# Sheet2.net
KiCad netlist of a schematic drawn in Altium Designer
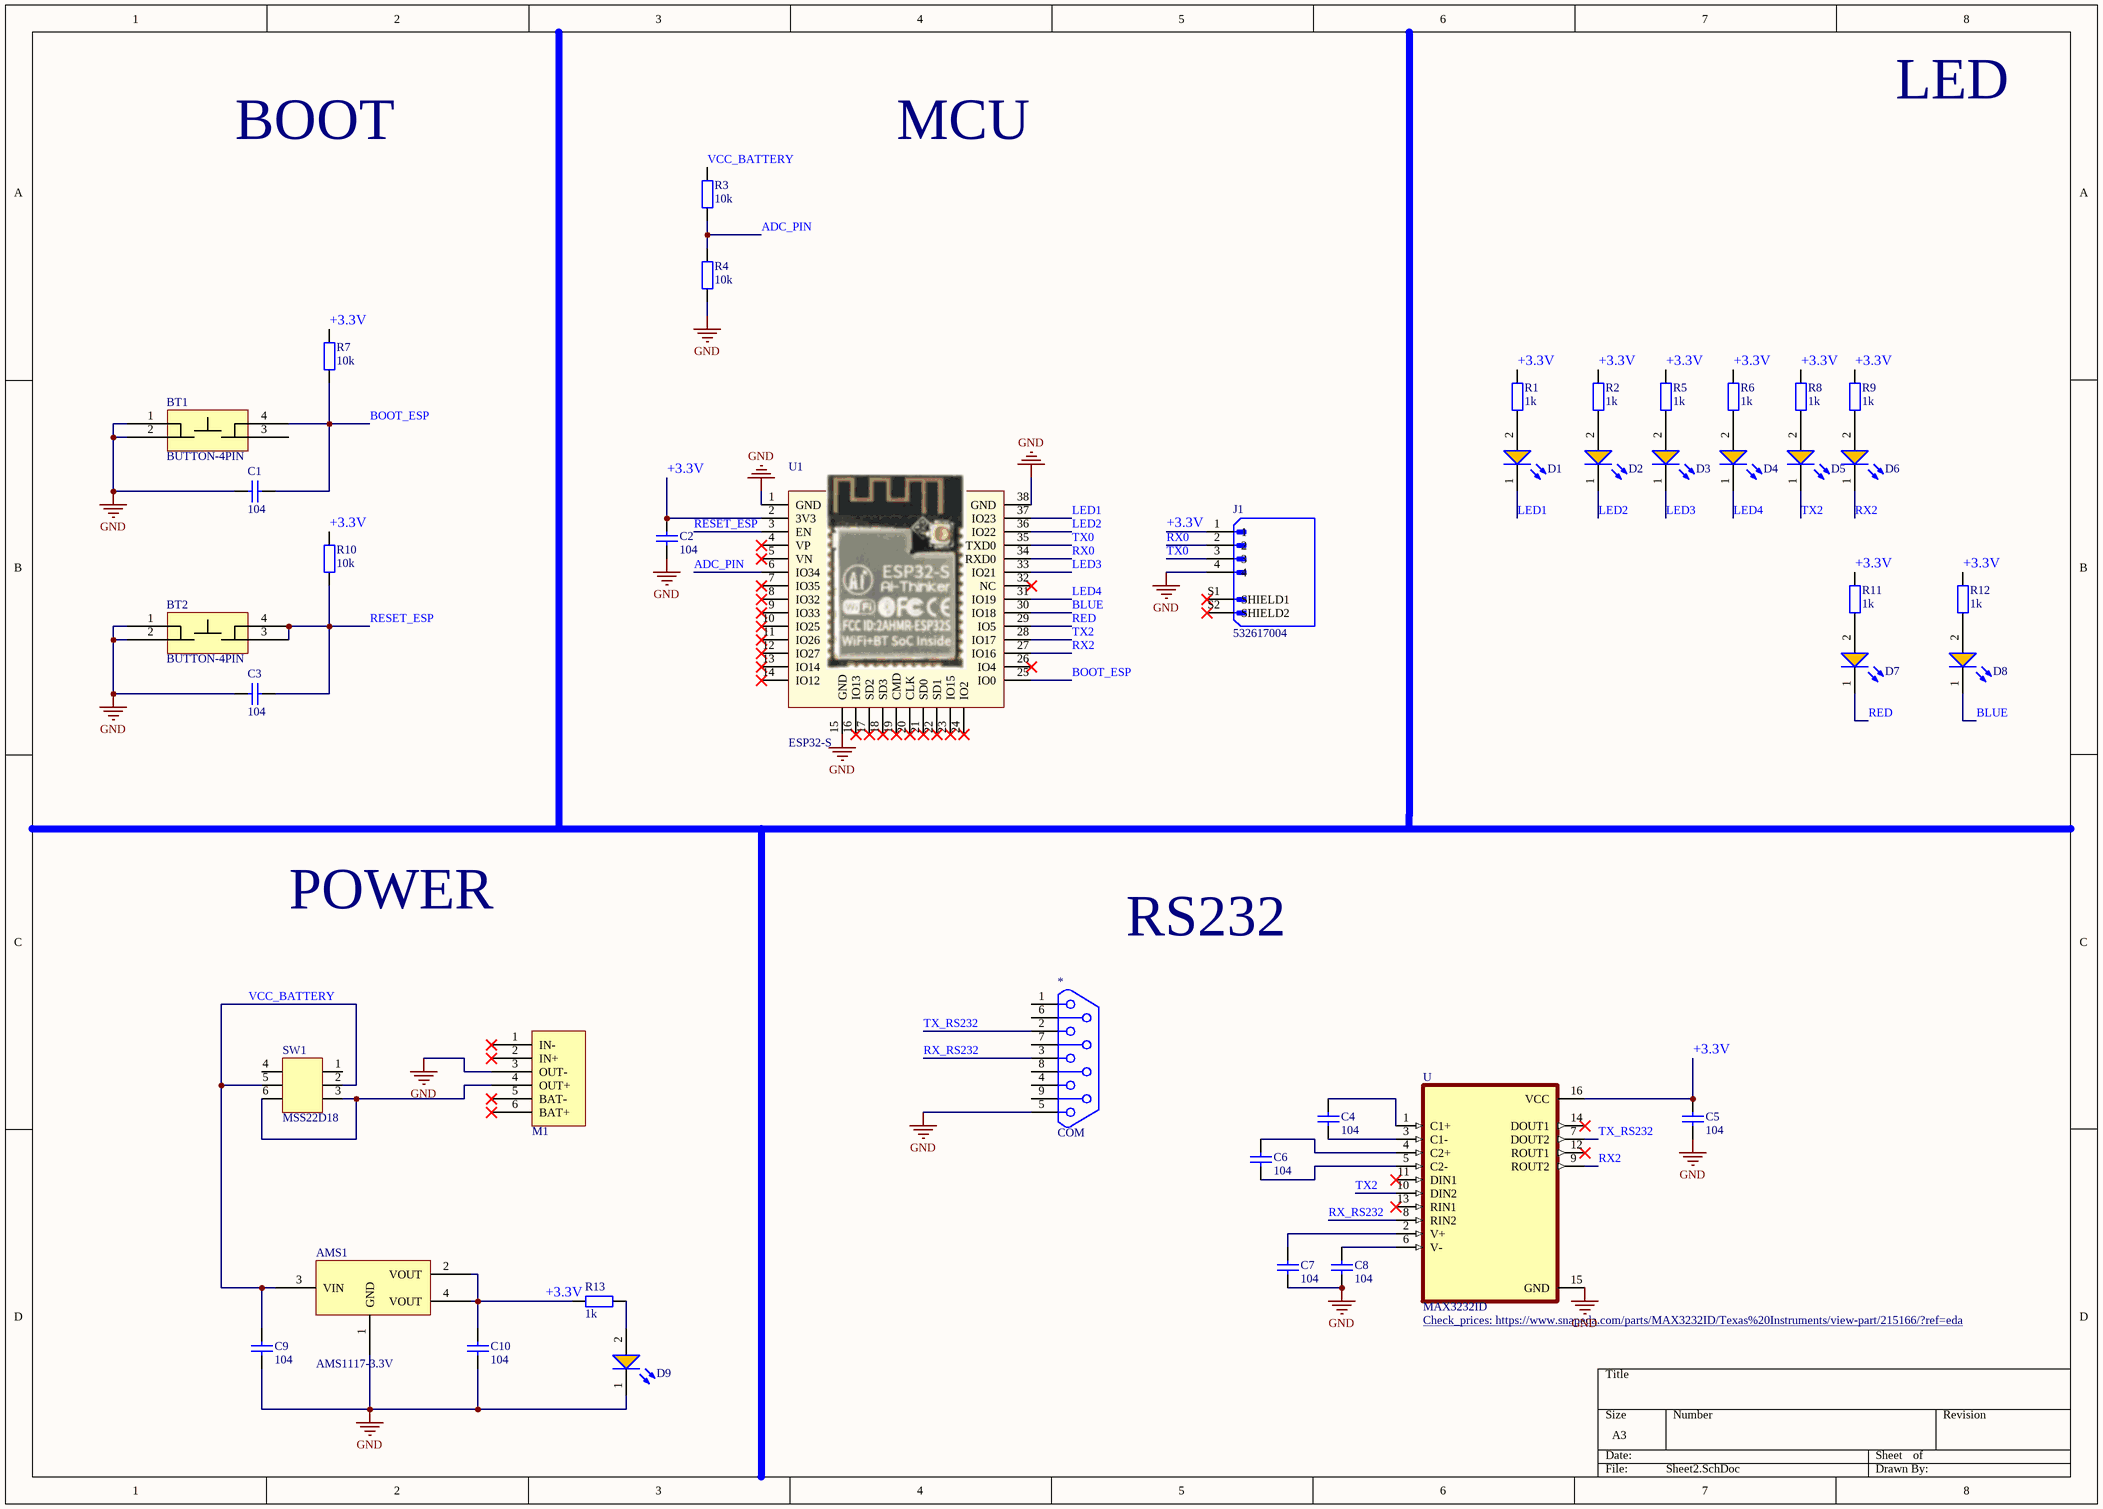
[diagram p0: Sheet2.SchDoc]

(export (version "E")
  (design (tool "Eeschema 10.0.6"))
  (components
    (comp (ref "*") (value "COM") (footprint "DSB 9-M") (libsource (lib "syhaunguyen") (part "COM")))
    (comp (ref "AMS1")
      (value "AMS1117-3.3V")
      (footprint "SOT223")
      (description "Dán")
      (libsource (lib "Altium_Lib_by_KhueNguyenCreator") (part "AMS1117 SMD"))
    )
    (comp (ref "BT1")
      (value "BUTTON-4PIN")
      (footprint "BUTTON-3X3X1.5-4PIN")
      (libsource (lib "THU_VIEN_1") (part "BUTTON-4PIN"))
    )
    (comp (ref "BT2")
      (value "BUTTON-4PIN")
      (footprint "BUTTON-3X3X1.5-4PIN")
      (libsource (lib "THU_VIEN_1") (part "BUTTON-4PIN"))
    )
    (comp (ref "C1")
      (value "104")
      (footprint "tu 0603")
      (description "Dán")
      (libsource (lib "Altium_Lib_by_KhueNguyenCreator") (part "Tu 0603 104 50V 10%"))
    )
    (comp (ref "C2")
      (value "104")
      (footprint "tu 0603")
      (description "Dán")
      (libsource (lib "Altium_Lib_by_KhueNguyenCreator") (part "Tu 0603 104 50V 10%"))
    )
    (comp (ref "C3")
      (value "104")
      (footprint "tu 0603")
      (description "Dán")
      (libsource (lib "Altium_Lib_by_KhueNguyenCreator") (part "Tu 0603 104 50V 10%"))
    )
    (comp (ref "C4")
      (value "104")
      (footprint "tu 0603")
      (description "Dán")
      (libsource (lib "Altium_Lib_by_KhueNguyenCreator") (part "Tu 0603 104 50V 10%"))
    )
    (comp (ref "C5")
      (value "104")
      (footprint "tu 0603")
      (description "Dán")
      (libsource (lib "Altium_Lib_by_KhueNguyenCreator") (part "Tu 0603 104 50V 10%"))
    )
    (comp (ref "C6")
      (value "104")
      (footprint "tu 0603")
      (description "Dán")
      (libsource (lib "Altium_Lib_by_KhueNguyenCreator") (part "Tu 0603 104 50V 10%"))
    )
    (comp (ref "C7")
      (value "104")
      (footprint "tu 0603")
      (description "Dán")
      (libsource (lib "Altium_Lib_by_KhueNguyenCreator") (part "Tu 0603 104 50V 10%"))
    )
    (comp (ref "C8")
      (value "104")
      (footprint "tu 0603")
      (description "Dán")
      (libsource (lib "Altium_Lib_by_KhueNguyenCreator") (part "Tu 0603 104 50V 10%"))
    )
    (comp (ref "C9")
      (value "104")
      (footprint "tu 0603")
      (description "Dán")
      (libsource (lib "Altium_Lib_by_KhueNguyenCreator") (part "Tu 0603 104 50V 10%"))
    )
    (comp (ref "C10")
      (value "104")
      (footprint "tu 0603")
      (description "Dán")
      (libsource (lib "Altium_Lib_by_KhueNguyenCreator") (part "Tu 0603 104 50V 10%"))
    )
    (comp (ref "D1")
      (value "Amber, 2V, 120°")
      (footprint "WL-SMSW_0603_L1.6W1H0.6")
      (description "WL-SMSW Mono-color Side View Waterclear, size 0603, Amber, 2V, 120°")
      (fields
        (field (name "MANUFACTURER PART NUMBER") "155060AS73200")
        (field (name "MANUFACTURER") "Wurth Elektronik")
      )
      (libsource (lib "Altium_WL-SMSW_rev22b") (part "155060AS73200"))
    )
    (comp (ref "D2")
      (value "Amber, 2V, 120°")
      (footprint "WL-SMSW_0603_L1.6W1H0.6")
      (description "WL-SMSW Mono-color Side View Waterclear, size 0603, Amber, 2V, 120°")
      (fields
        (field (name "MANUFACTURER PART NUMBER") "155060AS73200")
        (field (name "MANUFACTURER") "Wurth Elektronik")
      )
      (libsource (lib "Altium_WL-SMSW_rev22b") (part "155060AS73200"))
    )
    (comp (ref "D3")
      (value "Amber, 2V, 120°")
      (footprint "WL-SMSW_0603_L1.6W1H0.6")
      (description "WL-SMSW Mono-color Side View Waterclear, size 0603, Amber, 2V, 120°")
      (fields
        (field (name "MANUFACTURER PART NUMBER") "155060AS73200")
        (field (name "MANUFACTURER") "Wurth Elektronik")
      )
      (libsource (lib "Altium_WL-SMSW_rev22b") (part "155060AS73200"))
    )
    (comp (ref "D4")
      (value "Amber, 2V, 120°")
      (footprint "WL-SMSW_0603_L1.6W1H0.6")
      (description "WL-SMSW Mono-color Side View Waterclear, size 0603, Amber, 2V, 120°")
      (fields
        (field (name "MANUFACTURER PART NUMBER") "155060AS73200")
        (field (name "MANUFACTURER") "Wurth Elektronik")
      )
      (libsource (lib "Altium_WL-SMSW_rev22b") (part "155060AS73200"))
    )
    (comp (ref "D5")
      (value "Amber, 2V, 120°")
      (footprint "WL-SMSW_0603_L1.6W1H0.6")
      (description "WL-SMSW Mono-color Side View Waterclear, size 0603, Amber, 2V, 120°")
      (fields
        (field (name "MANUFACTURER PART NUMBER") "155060AS73200")
        (field (name "MANUFACTURER") "Wurth Elektronik")
      )
      (libsource (lib "Altium_WL-SMSW_rev22b") (part "155060AS73200"))
    )
    (comp (ref "D6")
      (value "Amber, 2V, 120°")
      (footprint "WL-SMSW_0603_L1.6W1H0.6")
      (description "WL-SMSW Mono-color Side View Waterclear, size 0603, Amber, 2V, 120°")
      (fields
        (field (name "MANUFACTURER PART NUMBER") "155060AS73200")
        (field (name "MANUFACTURER") "Wurth Elektronik")
      )
      (libsource (lib "Altium_WL-SMSW_rev22b") (part "155060AS73200"))
    )
    (comp (ref "D7")
      (value "Amber, 2V, 120°")
      (footprint "WL-SMSW_0603_L1.6W1H0.6")
      (description "WL-SMSW Mono-color Side View Waterclear, size 0603, Amber, 2V, 120°")
      (fields
        (field (name "MANUFACTURER PART NUMBER") "155060AS73200")
        (field (name "MANUFACTURER") "Wurth Elektronik")
      )
      (libsource (lib "Altium_WL-SMSW_rev22b") (part "155060AS73200"))
    )
    (comp (ref "D8")
      (value "Amber, 2V, 120°")
      (footprint "WL-SMSW_0603_L1.6W1H0.6")
      (description "WL-SMSW Mono-color Side View Waterclear, size 0603, Amber, 2V, 120°")
      (fields
        (field (name "MANUFACTURER PART NUMBER") "155060AS73200")
        (field (name "MANUFACTURER") "Wurth Elektronik")
      )
      (libsource (lib "Altium_WL-SMSW_rev22b") (part "155060AS73200"))
    )
    (comp (ref "D9")
      (value "Amber, 2V, 120°")
      (footprint "WL-SMSW_0603_L1.6W1H0.6")
      (description "WL-SMSW Mono-color Side View Waterclear, size 0603, Amber, 2V, 120°")
      (fields
        (field (name "MANUFACTURER PART NUMBER") "155060AS73200")
        (field (name "MANUFACTURER") "Wurth Elektronik")
      )
      (libsource (lib "Altium_WL-SMSW_rev22b") (part "155060AS73200"))
    )
    (comp (ref "J1")
      (value "532617004")
      (footprint "MOLEX_532617004")
      (libsource (lib "Header_4P") (part "532617004"))
    )
    (comp (ref "M1")
      (value "MODULE-TP4056")
      (footprint "MODULE-TP4056")
      (libsource (lib "MODULE") (part "MODULE-TP4056"))
    )
    (comp (ref "R1")
      (value "1k")
      (footprint "tro smd 0603")
      (description "Dán")
      (libsource (lib "Altium_Lib_by_KhueNguyenCreator") (part "Tro 0603 5% 1k"))
    )
    (comp (ref "R2")
      (value "1k")
      (footprint "tro smd 0603")
      (description "Dán")
      (libsource (lib "Altium_Lib_by_KhueNguyenCreator") (part "Tro 0603 5% 1k"))
    )
    (comp (ref "R3")
      (value "10k")
      (footprint "Tro SMD 0805")
      (description "Dán")
      (libsource (lib "Altium_Lib_by_KhueNguyenCreator") (part "Tro 0805 5% 82k"))
    )
    (comp (ref "R4")
      (value "10k")
      (footprint "Tro SMD 0805")
      (description "Dán")
      (libsource (lib "Altium_Lib_by_KhueNguyenCreator") (part "Tro 0805 5% 82k"))
    )
    (comp (ref "R5")
      (value "1k")
      (footprint "tro smd 0603")
      (description "Dán")
      (libsource (lib "Altium_Lib_by_KhueNguyenCreator") (part "Tro 0603 5% 1k"))
    )
    (comp (ref "R6")
      (value "1k")
      (footprint "tro smd 0603")
      (description "Dán")
      (libsource (lib "Altium_Lib_by_KhueNguyenCreator") (part "Tro 0603 5% 1k"))
    )
    (comp (ref "R7")
      (value "10k")
      (footprint "tro smd 0603")
      (description "Dán")
      (libsource (lib "Altium_Lib_by_KhueNguyenCreator") (part "Tro 0603 5% 1k"))
    )
    (comp (ref "R8")
      (value "1k")
      (footprint "tro smd 0603")
      (description "Dán")
      (libsource (lib "Altium_Lib_by_KhueNguyenCreator") (part "Tro 0603 5% 1k"))
    )
    (comp (ref "R9")
      (value "1k")
      (footprint "tro smd 0603")
      (description "Dán")
      (libsource (lib "Altium_Lib_by_KhueNguyenCreator") (part "Tro 0603 5% 1k"))
    )
    (comp (ref "R10")
      (value "10k")
      (footprint "tro smd 0603")
      (description "Dán")
      (libsource (lib "Altium_Lib_by_KhueNguyenCreator") (part "Tro 0603 5% 1k"))
    )
    (comp (ref "R11")
      (value "1k")
      (footprint "tro smd 0603")
      (description "Dán")
      (libsource (lib "Altium_Lib_by_KhueNguyenCreator") (part "Tro 0603 5% 1k"))
    )
    (comp (ref "R12")
      (value "1k")
      (footprint "tro smd 0603")
      (description "Dán")
      (libsource (lib "Altium_Lib_by_KhueNguyenCreator") (part "Tro 0603 5% 1k"))
    )
    (comp (ref "R13")
      (value "1k")
      (footprint "tro smd 0603")
      (description "Dán")
      (libsource (lib "Altium_Lib_by_KhueNguyenCreator") (part "Tro 0603 5% 1k"))
    )
    (comp (ref "SW1")
      (value "MSS22D18")
      (footprint "MSS22D18 SMD")
      (description "SMD")
      (libsource (lib "THU_VIEN_1") (part "MSS22D18"))
    )
    (comp (ref "U")
      (value "MAX3232ID")
      (footprint "SOIC127P600X175-16N")
      (description "3-V to 5.5-V multichannel RS-232 line driver & receiver 16-SOIC -40 to 85")
      (fields
        (field (name "MF") "Texas Instruments")
        (field (name "CHECK_PRICES") "https://www.snapeda.com/parts/MAX3232ID/Texas%20Instruments/view-part/215166/?ref=eda")
      )
      (libsource (lib "MAX3232ID") (part "MAX3232ID"))
    )
    (comp (ref "U1")
      (value "ESP32-S")
      (footprint "ESP-32WR")
      (libsource (lib "thuvienESP32") (part "ESP32-S"))
    )
  )
  (nets
    (net (code "1") (name "/+3.3V") (class "Default")
      (node (ref "AMS1") (pin "2") (pinfunction "VOUT_2") (pintype "passive"))
      (node (ref "AMS1") (pin "4") (pinfunction "VOUT_4") (pintype "passive"))
      (node (ref "C10") (pin "1") (pinfunction "1_1") (pintype "passive"))
      (node (ref "C2") (pin "1") (pinfunction "1_1") (pintype "passive"))
      (node (ref "C5") (pin "1") (pinfunction "1_1") (pintype "passive"))
      (node (ref "J1") (pin "1") (pinfunction "1_1") (pintype "passive"))
      (node (ref "R1") (pin "2") (pinfunction "2_2") (pintype "passive"))
      (node (ref "R10") (pin "2") (pinfunction "2_2") (pintype "passive"))
      (node (ref "R11") (pin "2") (pinfunction "2_2") (pintype "passive"))
      (node (ref "R12") (pin "2") (pinfunction "2_2") (pintype "passive"))
      (node (ref "R13") (pin "2") (pinfunction "2_2") (pintype "passive"))
      (node (ref "R2") (pin "2") (pinfunction "2_2") (pintype "passive"))
      (node (ref "R5") (pin "2") (pinfunction "2_2") (pintype "passive"))
      (node (ref "R6") (pin "2") (pinfunction "2_2") (pintype "passive"))
      (node (ref "R7") (pin "2") (pinfunction "2_2") (pintype "passive"))
      (node (ref "R8") (pin "2") (pinfunction "2_2") (pintype "passive"))
      (node (ref "R9") (pin "2") (pinfunction "2_2") (pintype "passive"))
      (node (ref "U") (pin "16") (pinfunction "VCC_16") (pintype "power_in"))
      (node (ref "U1") (pin "2") (pinfunction "3V3_2") (pintype "passive"))
    )
    (net (code "2") (name "/ADC_PIN") (class "Default")
      (node (ref "R3") (pin "1") (pinfunction "1_1") (pintype "passive"))
      (node (ref "R4") (pin "2") (pinfunction "2_2") (pintype "passive"))
      (node (ref "U1") (pin "6") (pinfunction "IO34_6") (pintype "passive"))
    )
    (net (code "3") (name "/BLUE") (class "Default")
      (node (ref "D8") (pin "1") (pinfunction "K_1") (pintype "passive"))
      (node (ref "U1") (pin "30") (pinfunction "IO18_30") (pintype "passive"))
    )
    (net (code "4") (name "/BOOT_ESP") (class "Default")
      (node (ref "BT1") (pin "4") (pinfunction "13_4") (pintype "passive"))
      (node (ref "C1") (pin "2") (pinfunction "2_2") (pintype "passive"))
      (node (ref "R7") (pin "1") (pinfunction "1_1") (pintype "passive"))
      (node (ref "U1") (pin "25") (pinfunction "IO0_25") (pintype "passive"))
    )
    (net (code "5") (name "/LED1") (class "Default")
      (node (ref "D1") (pin "1") (pinfunction "K_1") (pintype "passive"))
      (node (ref "U1") (pin "37") (pinfunction "IO23_37") (pintype "passive"))
    )
    (net (code "6") (name "/LED2") (class "Default")
      (node (ref "D2") (pin "1") (pinfunction "K_1") (pintype "passive"))
      (node (ref "U1") (pin "36") (pinfunction "IO22_36") (pintype "passive"))
    )
    (net (code "7") (name "/LED3") (class "Default")
      (node (ref "D3") (pin "1") (pinfunction "K_1") (pintype "passive"))
      (node (ref "U1") (pin "33") (pinfunction "IO21_33") (pintype "passive"))
    )
    (net (code "8") (name "/LED4") (class "Default")
      (node (ref "D4") (pin "1") (pinfunction "K_1") (pintype "passive"))
      (node (ref "U1") (pin "31") (pinfunction "IO19_31") (pintype "passive"))
    )
    (net (code "9") (name "/RED") (class "Default")
      (node (ref "D7") (pin "1") (pinfunction "K_1") (pintype "passive"))
      (node (ref "U1") (pin "29") (pinfunction "IO5_29") (pintype "passive"))
    )
    (net (code "10") (name "/RESET_ESP") (class "Default")
      (node (ref "BT2") (pin "3") (pinfunction "14_3") (pintype "passive"))
      (node (ref "BT2") (pin "4") (pinfunction "13_4") (pintype "passive"))
      (node (ref "C3") (pin "2") (pinfunction "2_2") (pintype "passive"))
      (node (ref "R10") (pin "1") (pinfunction "1_1") (pintype "passive"))
      (node (ref "U1") (pin "3") (pinfunction "EN_3") (pintype "passive"))
    )
    (net (code "11") (name "/RX0") (class "Default")
      (node (ref "J1") (pin "2") (pinfunction "2_2") (pintype "passive"))
      (node (ref "U1") (pin "34") (pinfunction "RXD0_34") (pintype "passive"))
    )
    (net (code "12") (name "/RX2") (class "Default")
      (node (ref "D6") (pin "1") (pinfunction "K_1") (pintype "passive"))
      (node (ref "U") (pin "9") (pinfunction "ROUT2_9") (pintype "output"))
      (node (ref "U1") (pin "27") (pinfunction "IO16_27") (pintype "passive"))
    )
    (net (code "13") (name "/RX_RS232") (class "Default")
      (node (ref "*") (pin "3") (pinfunction "3_3") (pintype "passive"))
      (node (ref "U") (pin "8") (pinfunction "RIN2_8") (pintype "input"))
    )
    (net (code "14") (name "/TX0") (class "Default")
      (node (ref "J1") (pin "3") (pinfunction "3_3") (pintype "passive"))
      (node (ref "U1") (pin "35") (pinfunction "TXD0_35") (pintype "passive"))
    )
    (net (code "15") (name "/TX2") (class "Default")
      (node (ref "D5") (pin "1") (pinfunction "K_1") (pintype "passive"))
      (node (ref "U") (pin "10") (pinfunction "DIN2_10") (pintype "input"))
      (node (ref "U1") (pin "28") (pinfunction "IO17_28") (pintype "passive"))
    )
    (net (code "16") (name "/TX_RS232") (class "Default")
      (node (ref "*") (pin "2") (pinfunction "2_2") (pintype "passive"))
      (node (ref "U") (pin "7") (pinfunction "DOUT2_7") (pintype "output"))
    )
    (net (code "17") (name "/VCC_BATTERY") (class "Default")
      (node (ref "AMS1") (pin "3") (pinfunction "VIN_3") (pintype "passive"))
      (node (ref "C9") (pin "1") (pinfunction "1_1") (pintype "passive"))
      (node (ref "R3") (pin "2") (pinfunction "2_2") (pintype "passive"))
      (node (ref "SW1") (pin "2") (pinfunction "78_2") (pintype "passive"))
      (node (ref "SW1") (pin "5") (pinfunction "81_5") (pintype "passive"))
    )
    (net (code "18") (name "GND") (class "Default")
      (node (ref "*") (pin "5") (pinfunction "5_5") (pintype "passive"))
      (node (ref "AMS1") (pin "1") (pinfunction "GND_1") (pintype "passive"))
      (node (ref "BT1") (pin "1") (pinfunction "11_1") (pintype "passive"))
      (node (ref "BT1") (pin "2") (pinfunction "12_2") (pintype "passive"))
      (node (ref "BT2") (pin "1") (pinfunction "11_1") (pintype "passive"))
      (node (ref "BT2") (pin "2") (pinfunction "12_2") (pintype "passive"))
      (node (ref "C1") (pin "1") (pinfunction "1_1") (pintype "passive"))
      (node (ref "C10") (pin "2") (pinfunction "2_2") (pintype "passive"))
      (node (ref "C2") (pin "2") (pinfunction "2_2") (pintype "passive"))
      (node (ref "C3") (pin "1") (pinfunction "1_1") (pintype "passive"))
      (node (ref "C5") (pin "2") (pinfunction "2_2") (pintype "passive"))
      (node (ref "C7") (pin "2") (pinfunction "2_2") (pintype "passive"))
      (node (ref "C8") (pin "2") (pinfunction "2_2") (pintype "passive"))
      (node (ref "C9") (pin "2") (pinfunction "2_2") (pintype "passive"))
      (node (ref "D9") (pin "1") (pinfunction "K_1") (pintype "passive"))
      (node (ref "J1") (pin "4") (pinfunction "4_4") (pintype "passive"))
      (node (ref "M1") (pin "3") (pinfunction "OUT-_3") (pintype "passive"))
      (node (ref "R4") (pin "1") (pinfunction "1_1") (pintype "passive"))
      (node (ref "U") (pin "15") (pinfunction "GND_15") (pintype "power_in"))
      (node (ref "U1") (pin "1") (pinfunction "GND_1") (pintype "passive"))
      (node (ref "U1") (pin "15") (pinfunction "GND_15") (pintype "passive"))
      (node (ref "U1") (pin "38") (pinfunction "GND_38") (pintype "passive"))
    )
    (net (code "19") (name "Net-(D1-A)") (class "Default")
      (node (ref "D1") (pin "2") (pinfunction "A_2") (pintype "passive"))
      (node (ref "R1") (pin "1") (pinfunction "1_1") (pintype "passive"))
    )
    (net (code "20") (name "Net-(D2-A)") (class "Default")
      (node (ref "D2") (pin "2") (pinfunction "A_2") (pintype "passive"))
      (node (ref "R2") (pin "1") (pinfunction "1_1") (pintype "passive"))
    )
    (net (code "21") (name "Net-(D3-A)") (class "Default")
      (node (ref "D3") (pin "2") (pinfunction "A_2") (pintype "passive"))
      (node (ref "R5") (pin "1") (pinfunction "1_1") (pintype "passive"))
    )
    (net (code "22") (name "Net-(D4-A)") (class "Default")
      (node (ref "D4") (pin "2") (pinfunction "A_2") (pintype "passive"))
      (node (ref "R6") (pin "1") (pinfunction "1_1") (pintype "passive"))
    )
    (net (code "23") (name "Net-(D5-A)") (class "Default")
      (node (ref "D5") (pin "2") (pinfunction "A_2") (pintype "passive"))
      (node (ref "R8") (pin "1") (pinfunction "1_1") (pintype "passive"))
    )
    (net (code "24") (name "Net-(D6-A)") (class "Default")
      (node (ref "D6") (pin "2") (pinfunction "A_2") (pintype "passive"))
      (node (ref "R9") (pin "1") (pinfunction "1_1") (pintype "passive"))
    )
    (net (code "25") (name "Net-(D7-A)") (class "Default")
      (node (ref "D7") (pin "2") (pinfunction "A_2") (pintype "passive"))
      (node (ref "R11") (pin "1") (pinfunction "1_1") (pintype "passive"))
    )
    (net (code "26") (name "Net-(D8-A)") (class "Default")
      (node (ref "D8") (pin "2") (pinfunction "A_2") (pintype "passive"))
      (node (ref "R12") (pin "1") (pinfunction "1_1") (pintype "passive"))
    )
    (net (code "27") (name "Net-(D9-A)") (class "Default")
      (node (ref "D9") (pin "2") (pinfunction "A_2") (pintype "passive"))
      (node (ref "R13") (pin "1") (pinfunction "1_1") (pintype "passive"))
    )
    (net (code "28") (name "Net-(M1-OUT+)") (class "Default")
      (node (ref "M1") (pin "4") (pinfunction "OUT+_4") (pintype "passive"))
      (node (ref "SW1") (pin "3") (pinfunction "79_3") (pintype "passive"))
      (node (ref "SW1") (pin "6") (pinfunction "82_6") (pintype "passive"))
    )
    (net (code "29") (name "Net-(U-C1+)") (class "Default")
      (node (ref "C4") (pin "1") (pinfunction "1_1") (pintype "passive"))
      (node (ref "U") (pin "1") (pinfunction "C1+_1") (pintype "input"))
    )
    (net (code "30") (name "Net-(U-C1-)") (class "Default")
      (node (ref "C4") (pin "2") (pinfunction "2_2") (pintype "passive"))
      (node (ref "U") (pin "3") (pinfunction "C1-_3") (pintype "input"))
    )
    (net (code "31") (name "Net-(U-C2+)") (class "Default")
      (node (ref "C6") (pin "1") (pinfunction "1_1") (pintype "passive"))
      (node (ref "U") (pin "4") (pinfunction "C2+_4") (pintype "input"))
    )
    (net (code "32") (name "Net-(U-C2-)") (class "Default")
      (node (ref "C6") (pin "2") (pinfunction "2_2") (pintype "passive"))
      (node (ref "U") (pin "5") (pinfunction "C2-_5") (pintype "input"))
    )
    (net (code "33") (name "Net-(U-V+)") (class "Default")
      (node (ref "C7") (pin "1") (pinfunction "1_1") (pintype "passive"))
      (node (ref "U") (pin "2") (pinfunction "V+_2") (pintype "input"))
    )
    (net (code "34") (name "Net-(U-V-)") (class "Default")
      (node (ref "C8") (pin "1") (pinfunction "1_1") (pintype "passive"))
      (node (ref "U") (pin "6") (pinfunction "V-_6") (pintype "input"))
    )
    (net (code "35") (name "unconnected-(*-Pad1)") (class "Default")
      (node (ref "*") (pin "1") (pinfunction "1_1") (pintype "passive"))
    )
    (net (code "36") (name "unconnected-(*-Pad4)") (class "Default")
      (node (ref "*") (pin "4") (pinfunction "4_4") (pintype "passive"))
    )
    (net (code "37") (name "unconnected-(*-Pad6)") (class "Default")
      (node (ref "*") (pin "6") (pinfunction "6_6") (pintype "passive"))
    )
    (net (code "38") (name "unconnected-(*-Pad7)") (class "Default")
      (node (ref "*") (pin "7") (pinfunction "7_7") (pintype "passive"))
    )
    (net (code "39") (name "unconnected-(*-Pad8)") (class "Default")
      (node (ref "*") (pin "8") (pinfunction "8_8") (pintype "passive"))
    )
    (net (code "40") (name "unconnected-(*-Pad9)") (class "Default")
      (node (ref "*") (pin "9") (pinfunction "9_9") (pintype "passive"))
    )
    (net (code "41") (name "unconnected-(BT1-14-Pad3)") (class "Default")
      (node (ref "BT1") (pin "3") (pinfunction "14_3") (pintype "passive"))
    )
    (net (code "42") (name "unconnected-(J1-SHIELD1-PadS1)") (class "Default")
      (node (ref "J1") (pin "S1") (pinfunction "SHIELD1_S1") (pintype "passive+no_connect"))
    )
    (net (code "43") (name "unconnected-(J1-SHIELD2-PadS2)") (class "Default")
      (node (ref "J1") (pin "S2") (pinfunction "SHIELD2_S2") (pintype "passive+no_connect"))
    )
    (net (code "44") (name "unconnected-(M1-BAT+-Pad6)") (class "Default")
      (node (ref "M1") (pin "6") (pinfunction "BAT+_6") (pintype "passive+no_connect"))
    )
    (net (code "45") (name "unconnected-(M1-BAT--Pad5)") (class "Default")
      (node (ref "M1") (pin "5") (pinfunction "BAT-_5") (pintype "passive+no_connect"))
    )
    (net (code "46") (name "unconnected-(M1-IN+-Pad2)") (class "Default")
      (node (ref "M1") (pin "2") (pinfunction "IN+_2") (pintype "passive+no_connect"))
    )
    (net (code "47") (name "unconnected-(M1-IN--Pad1)") (class "Default")
      (node (ref "M1") (pin "1") (pinfunction "IN-_1") (pintype "passive+no_connect"))
    )
    (net (code "48") (name "unconnected-(SW1-77-Pad1)") (class "Default")
      (node (ref "SW1") (pin "1") (pinfunction "77_1") (pintype "passive"))
    )
    (net (code "49") (name "unconnected-(SW1-Pad4)") (class "Default")
      (node (ref "SW1") (pin "4") (pintype "passive"))
    )
    (net (code "50") (name "unconnected-(U-DIN1-Pad11)") (class "Default")
      (node (ref "U") (pin "11") (pinfunction "DIN1_11") (pintype "input+no_connect"))
    )
    (net (code "51") (name "unconnected-(U-DOUT1-Pad14)") (class "Default")
      (node (ref "U") (pin "14") (pinfunction "DOUT1_14") (pintype "output+no_connect"))
    )
    (net (code "52") (name "unconnected-(U-RIN1-Pad13)") (class "Default")
      (node (ref "U") (pin "13") (pinfunction "RIN1_13") (pintype "input+no_connect"))
    )
    (net (code "53") (name "unconnected-(U-ROUT1-Pad12)") (class "Default")
      (node (ref "U") (pin "12") (pinfunction "ROUT1_12") (pintype "output+no_connect"))
    )
    (net (code "54") (name "unconnected-(U1-CLK-Pad20)") (class "Default")
      (node (ref "U1") (pin "20") (pinfunction "CLK_20") (pintype "passive+no_connect"))
    )
    (net (code "55") (name "unconnected-(U1-CMD-Pad19)") (class "Default")
      (node (ref "U1") (pin "19") (pinfunction "CMD_19") (pintype "passive+no_connect"))
    )
    (net (code "56") (name "unconnected-(U1-IO2-Pad24)") (class "Default")
      (node (ref "U1") (pin "24") (pinfunction "IO2_24") (pintype "passive+no_connect"))
    )
    (net (code "57") (name "unconnected-(U1-IO4-Pad26)") (class "Default")
      (node (ref "U1") (pin "26") (pinfunction "IO4_26") (pintype "passive+no_connect"))
    )
    (net (code "58") (name "unconnected-(U1-IO12-Pad14)") (class "Default")
      (node (ref "U1") (pin "14") (pinfunction "IO12_14") (pintype "passive+no_connect"))
    )
    (net (code "59") (name "unconnected-(U1-IO13-Pad16)") (class "Default")
      (node (ref "U1") (pin "16") (pinfunction "IO13_16") (pintype "passive+no_connect"))
    )
    (net (code "60") (name "unconnected-(U1-IO14-Pad13)") (class "Default")
      (node (ref "U1") (pin "13") (pinfunction "IO14_13") (pintype "passive+no_connect"))
    )
    (net (code "61") (name "unconnected-(U1-IO15-Pad23)") (class "Default")
      (node (ref "U1") (pin "23") (pinfunction "IO15_23") (pintype "passive+no_connect"))
    )
    (net (code "62") (name "unconnected-(U1-IO25-Pad10)") (class "Default")
      (node (ref "U1") (pin "10") (pinfunction "IO25_10") (pintype "passive+no_connect"))
    )
    (net (code "63") (name "unconnected-(U1-IO26-Pad11)") (class "Default")
      (node (ref "U1") (pin "11") (pinfunction "IO26_11") (pintype "passive+no_connect"))
    )
    (net (code "64") (name "unconnected-(U1-IO27-Pad12)") (class "Default")
      (node (ref "U1") (pin "12") (pinfunction "IO27_12") (pintype "passive+no_connect"))
    )
    (net (code "65") (name "unconnected-(U1-IO32-Pad8)") (class "Default")
      (node (ref "U1") (pin "8") (pinfunction "IO32_8") (pintype "passive+no_connect"))
    )
    (net (code "66") (name "unconnected-(U1-IO33-Pad9)") (class "Default")
      (node (ref "U1") (pin "9") (pinfunction "IO33_9") (pintype "passive+no_connect"))
    )
    (net (code "67") (name "unconnected-(U1-IO35-Pad7)") (class "Default")
      (node (ref "U1") (pin "7") (pinfunction "IO35_7") (pintype "passive+no_connect"))
    )
    (net (code "68") (name "unconnected-(U1-NC-Pad32)") (class "Default")
      (node (ref "U1") (pin "32") (pinfunction "NC_32") (pintype "passive+no_connect"))
    )
    (net (code "69") (name "unconnected-(U1-SD0-Pad21)") (class "Default")
      (node (ref "U1") (pin "21") (pinfunction "SD0_21") (pintype "passive+no_connect"))
    )
    (net (code "70") (name "unconnected-(U1-SD1-Pad22)") (class "Default")
      (node (ref "U1") (pin "22") (pinfunction "SD1_22") (pintype "passive+no_connect"))
    )
    (net (code "71") (name "unconnected-(U1-SD2-Pad17)") (class "Default")
      (node (ref "U1") (pin "17") (pinfunction "SD2_17") (pintype "passive+no_connect"))
    )
    (net (code "72") (name "unconnected-(U1-SD3-Pad18)") (class "Default")
      (node (ref "U1") (pin "18") (pinfunction "SD3_18") (pintype "passive+no_connect"))
    )
    (net (code "73") (name "unconnected-(U1-VN-Pad5)") (class "Default")
      (node (ref "U1") (pin "5") (pinfunction "VN_5") (pintype "passive+no_connect"))
    )
    (net (code "74") (name "unconnected-(U1-VP-Pad4)") (class "Default")
      (node (ref "U1") (pin "4") (pinfunction "VP_4") (pintype "passive+no_connect"))
    )
  )
)
